# -modifi.net
KiCad netlist of a schematic drawn in Altium Designer
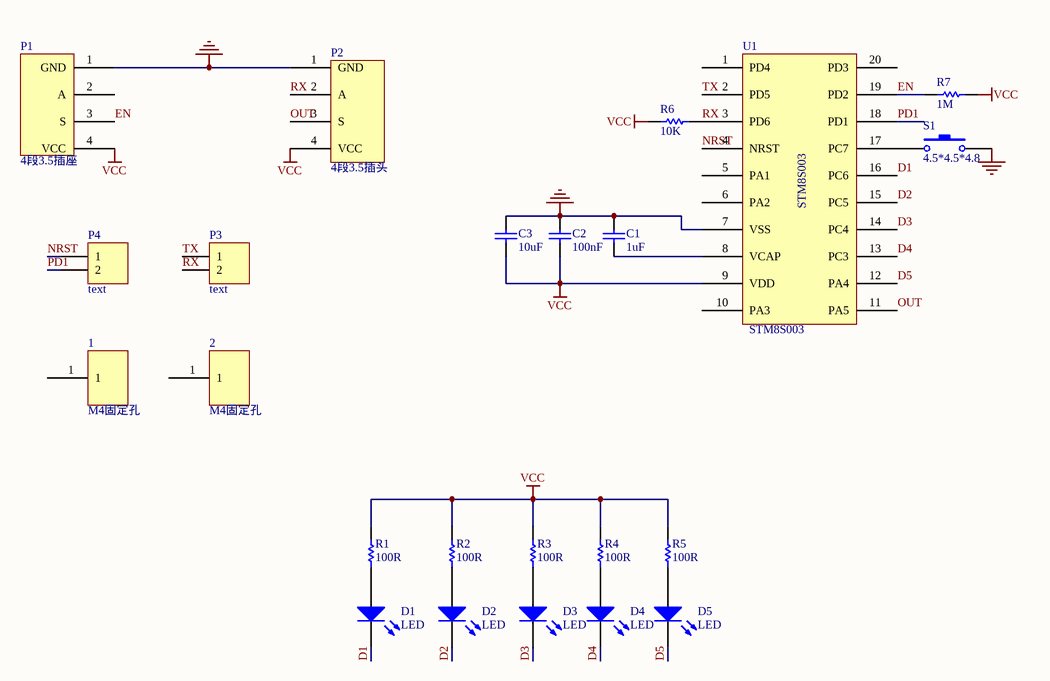
[diagram p0: 条形灯-modifi.SchDoc]

(export (version "E")
  (design (tool "Eeschema 10.0.6"))
  (components
    (comp (ref "1") (value "M4固定孔") (footprint "M4固定孔") (libsource (lib "DDL6.30") (part "M4固定孔")))
    (comp (ref "2") (value "M4固定孔") (footprint "M4固定孔") (libsource (lib "DDL6.30") (part "M4固定孔")))
    (comp (ref "C1")
      (value "1uF")
      (footprint "0603C")
      (description "Capacitor")
      (fields (field (name "PUBLISHER") "Altium Limited"))
      (libsource (lib "Miscellaneous Devices") (part "Cap"))
    )
    (comp (ref "C2")
      (value "100nF")
      (footprint "0603C")
      (description "Capacitor")
      (fields (field (name "PUBLISHER") "Altium Limited"))
      (libsource (lib "Miscellaneous Devices") (part "Cap"))
    )
    (comp (ref "C3")
      (value "10uF")
      (footprint "0603C")
      (description "Capacitor")
      (fields (field (name "PUBLISHER") "Altium Limited"))
      (libsource (lib "Miscellaneous Devices") (part "Cap"))
    )
    (comp (ref "D1")
      (value "LED")
      (footprint "3528LED")
      (description "Typical INFRARED GaAs LED")
      (fields (field (name "PUBLISHER") "Altium Limited"))
      (libsource (lib "Miscellaneous Devices") (part "LED0"))
    )
    (comp (ref "D2")
      (value "LED")
      (footprint "3528LED")
      (description "Typical INFRARED GaAs LED")
      (fields (field (name "PUBLISHER") "Altium Limited"))
      (libsource (lib "Miscellaneous Devices") (part "LED0"))
    )
    (comp (ref "D3")
      (value "LED")
      (footprint "3528LED")
      (description "Typical INFRARED GaAs LED")
      (fields (field (name "PUBLISHER") "Altium Limited"))
      (libsource (lib "Miscellaneous Devices") (part "LED0"))
    )
    (comp (ref "D4")
      (value "LED")
      (footprint "3528LED")
      (description "Typical INFRARED GaAs LED")
      (fields (field (name "PUBLISHER") "Altium Limited"))
      (libsource (lib "Miscellaneous Devices") (part "LED0"))
    )
    (comp (ref "D5")
      (value "LED")
      (footprint "3528LED")
      (description "Typical INFRARED GaAs LED")
      (fields (field (name "PUBLISHER") "Altium Limited"))
      (libsource (lib "Miscellaneous Devices") (part "LED0"))
    )
    (comp (ref "P1") (value "4段3.5插座") (footprint "4段3.5耳机贴片座") (libsource (lib "DDL6.30") (part "4段3.5插座")))
    (comp (ref "P2") (value "4段3.5插头") (footprint "4段3.5插头") (libsource (lib "DDL6.30") (part "4段3.5插头")))
    (comp (ref "P3")
      (value "text")
      (footprint "2SMT-2.54")
      (description "Header, 2-Pin")
      (fields (field (name "PUBLISHER") "Altium Limited"))
      (libsource (lib "Miscellaneous Connectors") (part "Header 2"))
    )
    (comp (ref "P4")
      (value "text")
      (footprint "2SMT-2.54")
      (description "Header, 2-Pin")
      (fields (field (name "PUBLISHER") "Altium Limited"))
      (libsource (lib "Miscellaneous Connectors") (part "Header 2"))
    )
    (comp (ref "R1")
      (value "100R")
      (footprint "0603R")
      (description "Resistor")
      (fields (field (name "PUBLISHER") "Altium Limited"))
      (libsource (lib "Miscellaneous Devices") (part "Res1"))
    )
    (comp (ref "R2")
      (value "100R")
      (footprint "0603R")
      (description "Resistor")
      (fields (field (name "PUBLISHER") "Altium Limited"))
      (libsource (lib "Miscellaneous Devices") (part "Res1"))
    )
    (comp (ref "R3")
      (value "100R")
      (footprint "0603R")
      (description "Resistor")
      (fields (field (name "PUBLISHER") "Altium Limited"))
      (libsource (lib "Miscellaneous Devices") (part "Res1"))
    )
    (comp (ref "R4")
      (value "100R")
      (footprint "0603R")
      (description "Resistor")
      (fields (field (name "PUBLISHER") "Altium Limited"))
      (libsource (lib "Miscellaneous Devices") (part "Res1"))
    )
    (comp (ref "R5")
      (value "100R")
      (footprint "0603R")
      (description "Resistor")
      (fields (field (name "PUBLISHER") "Altium Limited"))
      (libsource (lib "Miscellaneous Devices") (part "Res1"))
    )
    (comp (ref "R6")
      (value "10K")
      (footprint "0603R")
      (description "Resistor")
      (fields (field (name "PUBLISHER") "Altium Limited"))
      (libsource (lib "Miscellaneous Devices") (part "Res1"))
    )
    (comp (ref "R7")
      (value "1M")
      (footprint "0603R")
      (description "Resistor")
      (fields (field (name "PUBLISHER") "Altium Limited"))
      (libsource (lib "Miscellaneous Devices") (part "Res1"))
    )
    (comp (ref "S1")
      (value "4.5*4.5*4.8")
      (footprint "按键4.5*4.5*4.8")
      (description "Switch")
      (fields (field (name "PUBLISHER") "Altium Limited"))
      (libsource (lib "Miscellaneous Devices") (part "SW-PB"))
    )
    (comp (ref "U1") (value "STM8S003") (footprint "TSSOP20") (libsource (lib "DDL6.30") (part "STM8S003")))
  )
  (nets
    (net (code "1") (name "/D1") (class "Default")
      (node (ref "D1") (pin "2") (pinfunction "K_2") (pintype "passive"))
      (node (ref "U1") (pin "16") (pinfunction "PC6_16") (pintype "passive"))
    )
    (net (code "2") (name "/D2") (class "Default")
      (node (ref "D2") (pin "2") (pinfunction "K_2") (pintype "passive"))
      (node (ref "U1") (pin "15") (pinfunction "PC5_15") (pintype "passive"))
    )
    (net (code "3") (name "/D3") (class "Default")
      (node (ref "D3") (pin "2") (pinfunction "K_2") (pintype "passive"))
      (node (ref "U1") (pin "14") (pinfunction "PC4_14") (pintype "passive"))
    )
    (net (code "4") (name "/D4") (class "Default")
      (node (ref "D4") (pin "2") (pinfunction "K_2") (pintype "passive"))
      (node (ref "U1") (pin "13") (pinfunction "PC3_13") (pintype "passive"))
    )
    (net (code "5") (name "/D5") (class "Default")
      (node (ref "D5") (pin "2") (pinfunction "K_2") (pintype "passive"))
      (node (ref "U1") (pin "12") (pinfunction "PA4_12") (pintype "passive"))
    )
    (net (code "6") (name "/EN") (class "Default")
      (node (ref "P1") (pin "3") (pinfunction "S_3") (pintype "passive"))
      (node (ref "R7") (pin "2") (pinfunction "2_2") (pintype "passive"))
      (node (ref "U1") (pin "19") (pinfunction "PD2_19") (pintype "passive"))
    )
    (net (code "7") (name "/NRST") (class "Default")
      (node (ref "P4") (pin "1") (pinfunction "1_1") (pintype "passive"))
      (node (ref "U1") (pin "4") (pinfunction "NRST_4") (pintype "passive"))
    )
    (net (code "8") (name "/OUT") (class "Default")
      (node (ref "P2") (pin "3") (pinfunction "S_3") (pintype "passive"))
      (node (ref "U1") (pin "11") (pinfunction "PA5_11") (pintype "passive"))
    )
    (net (code "9") (name "/PD1") (class "Default")
      (node (ref "P4") (pin "2") (pinfunction "2_2") (pintype "passive"))
      (node (ref "U1") (pin "18") (pinfunction "PD1_18") (pintype "passive"))
    )
    (net (code "10") (name "/RX") (class "Default")
      (node (ref "P2") (pin "2") (pinfunction "A_2") (pintype "passive"))
      (node (ref "P3") (pin "2") (pinfunction "2_2") (pintype "passive"))
      (node (ref "R6") (pin "1") (pinfunction "1_1") (pintype "passive"))
      (node (ref "U1") (pin "3") (pinfunction "PD6_3") (pintype "passive"))
    )
    (net (code "11") (name "/TX") (class "Default")
      (node (ref "P3") (pin "1") (pinfunction "1_1") (pintype "passive"))
      (node (ref "U1") (pin "2") (pinfunction "PD5_2") (pintype "passive"))
    )
    (net (code "12") (name "GND") (class "Default")
      (node (ref "C1") (pin "2") (pinfunction "2_2") (pintype "passive"))
      (node (ref "C2") (pin "2") (pinfunction "2_2") (pintype "passive"))
      (node (ref "C3") (pin "2") (pinfunction "2_2") (pintype "passive"))
      (node (ref "P1") (pin "1") (pinfunction "GND_1") (pintype "passive"))
      (node (ref "P2") (pin "1") (pinfunction "GND_1") (pintype "passive"))
      (node (ref "S1") (pin "2") (pinfunction "2_2") (pintype "passive"))
      (node (ref "U1") (pin "7") (pinfunction "VSS_7") (pintype "passive"))
    )
    (net (code "13") (name "Net-(D1-A)") (class "Default")
      (node (ref "D1") (pin "1") (pinfunction "A_1") (pintype "passive"))
      (node (ref "R1") (pin "1") (pinfunction "1_1") (pintype "passive"))
    )
    (net (code "14") (name "Net-(D2-A)") (class "Default")
      (node (ref "D2") (pin "1") (pinfunction "A_1") (pintype "passive"))
      (node (ref "R2") (pin "1") (pinfunction "1_1") (pintype "passive"))
    )
    (net (code "15") (name "Net-(D3-A)") (class "Default")
      (node (ref "D3") (pin "1") (pinfunction "A_1") (pintype "passive"))
      (node (ref "R3") (pin "1") (pinfunction "1_1") (pintype "passive"))
    )
    (net (code "16") (name "Net-(D4-A)") (class "Default")
      (node (ref "D4") (pin "1") (pinfunction "A_1") (pintype "passive"))
      (node (ref "R4") (pin "1") (pinfunction "1_1") (pintype "passive"))
    )
    (net (code "17") (name "Net-(D5-A)") (class "Default")
      (node (ref "D5") (pin "1") (pinfunction "A_1") (pintype "passive"))
      (node (ref "R5") (pin "1") (pinfunction "1_1") (pintype "passive"))
    )
    (net (code "18") (name "Net-(U1-PC7)") (class "Default")
      (node (ref "S1") (pin "1") (pinfunction "1_1") (pintype "passive"))
      (node (ref "U1") (pin "17") (pinfunction "PC7_17") (pintype "passive"))
    )
    (net (code "19") (name "Net-(U1-VCAP)") (class "Default")
      (node (ref "C1") (pin "1") (pinfunction "1_1") (pintype "passive"))
      (node (ref "U1") (pin "8") (pinfunction "VCAP_8") (pintype "passive"))
    )
    (net (code "20") (name "VCC") (class "Default")
      (node (ref "C2") (pin "1") (pinfunction "1_1") (pintype "passive"))
      (node (ref "C3") (pin "1") (pinfunction "1_1") (pintype "passive"))
      (node (ref "P1") (pin "4") (pinfunction "VCC_4") (pintype "passive"))
      (node (ref "P2") (pin "4") (pinfunction "VCC_4") (pintype "passive"))
      (node (ref "R1") (pin "2") (pinfunction "2_2") (pintype "passive"))
      (node (ref "R2") (pin "2") (pinfunction "2_2") (pintype "passive"))
      (node (ref "R3") (pin "2") (pinfunction "2_2") (pintype "passive"))
      (node (ref "R4") (pin "2") (pinfunction "2_2") (pintype "passive"))
      (node (ref "R5") (pin "2") (pinfunction "2_2") (pintype "passive"))
      (node (ref "R6") (pin "2") (pinfunction "2_2") (pintype "passive"))
      (node (ref "R7") (pin "1") (pinfunction "1_1") (pintype "passive"))
      (node (ref "U1") (pin "9") (pinfunction "VDD_9") (pintype "passive"))
    )
    (net (code "21") (name "unconnected-(1-Pad1)") (class "Default")
      (node (ref "1") (pin "1") (pinfunction "1_1") (pintype "passive"))
    )
    (net (code "22") (name "unconnected-(2-Pad1)") (class "Default")
      (node (ref "2") (pin "1") (pinfunction "1_1") (pintype "passive"))
    )
    (net (code "23") (name "unconnected-(P1-A-Pad2)") (class "Default")
      (node (ref "P1") (pin "2") (pinfunction "A_2") (pintype "passive"))
    )
    (net (code "24") (name "unconnected-(U1-PA1-Pad5)") (class "Default")
      (node (ref "U1") (pin "5") (pinfunction "PA1_5") (pintype "passive"))
    )
    (net (code "25") (name "unconnected-(U1-PA2-Pad6)") (class "Default")
      (node (ref "U1") (pin "6") (pinfunction "PA2_6") (pintype "passive"))
    )
    (net (code "26") (name "unconnected-(U1-PA3-Pad10)") (class "Default")
      (node (ref "U1") (pin "10") (pinfunction "PA3_10") (pintype "passive"))
    )
    (net (code "27") (name "unconnected-(U1-PD3-Pad20)") (class "Default")
      (node (ref "U1") (pin "20") (pinfunction "PD3_20") (pintype "passive"))
    )
    (net (code "28") (name "unconnected-(U1-PD4-Pad1)") (class "Default")
      (node (ref "U1") (pin "1") (pinfunction "PD4_1") (pintype "passive"))
    )
  )
)
